# RS485_Demo_Bord_v1_0_-.net
KiCad netlist of a schematic drawn in Altium Designer
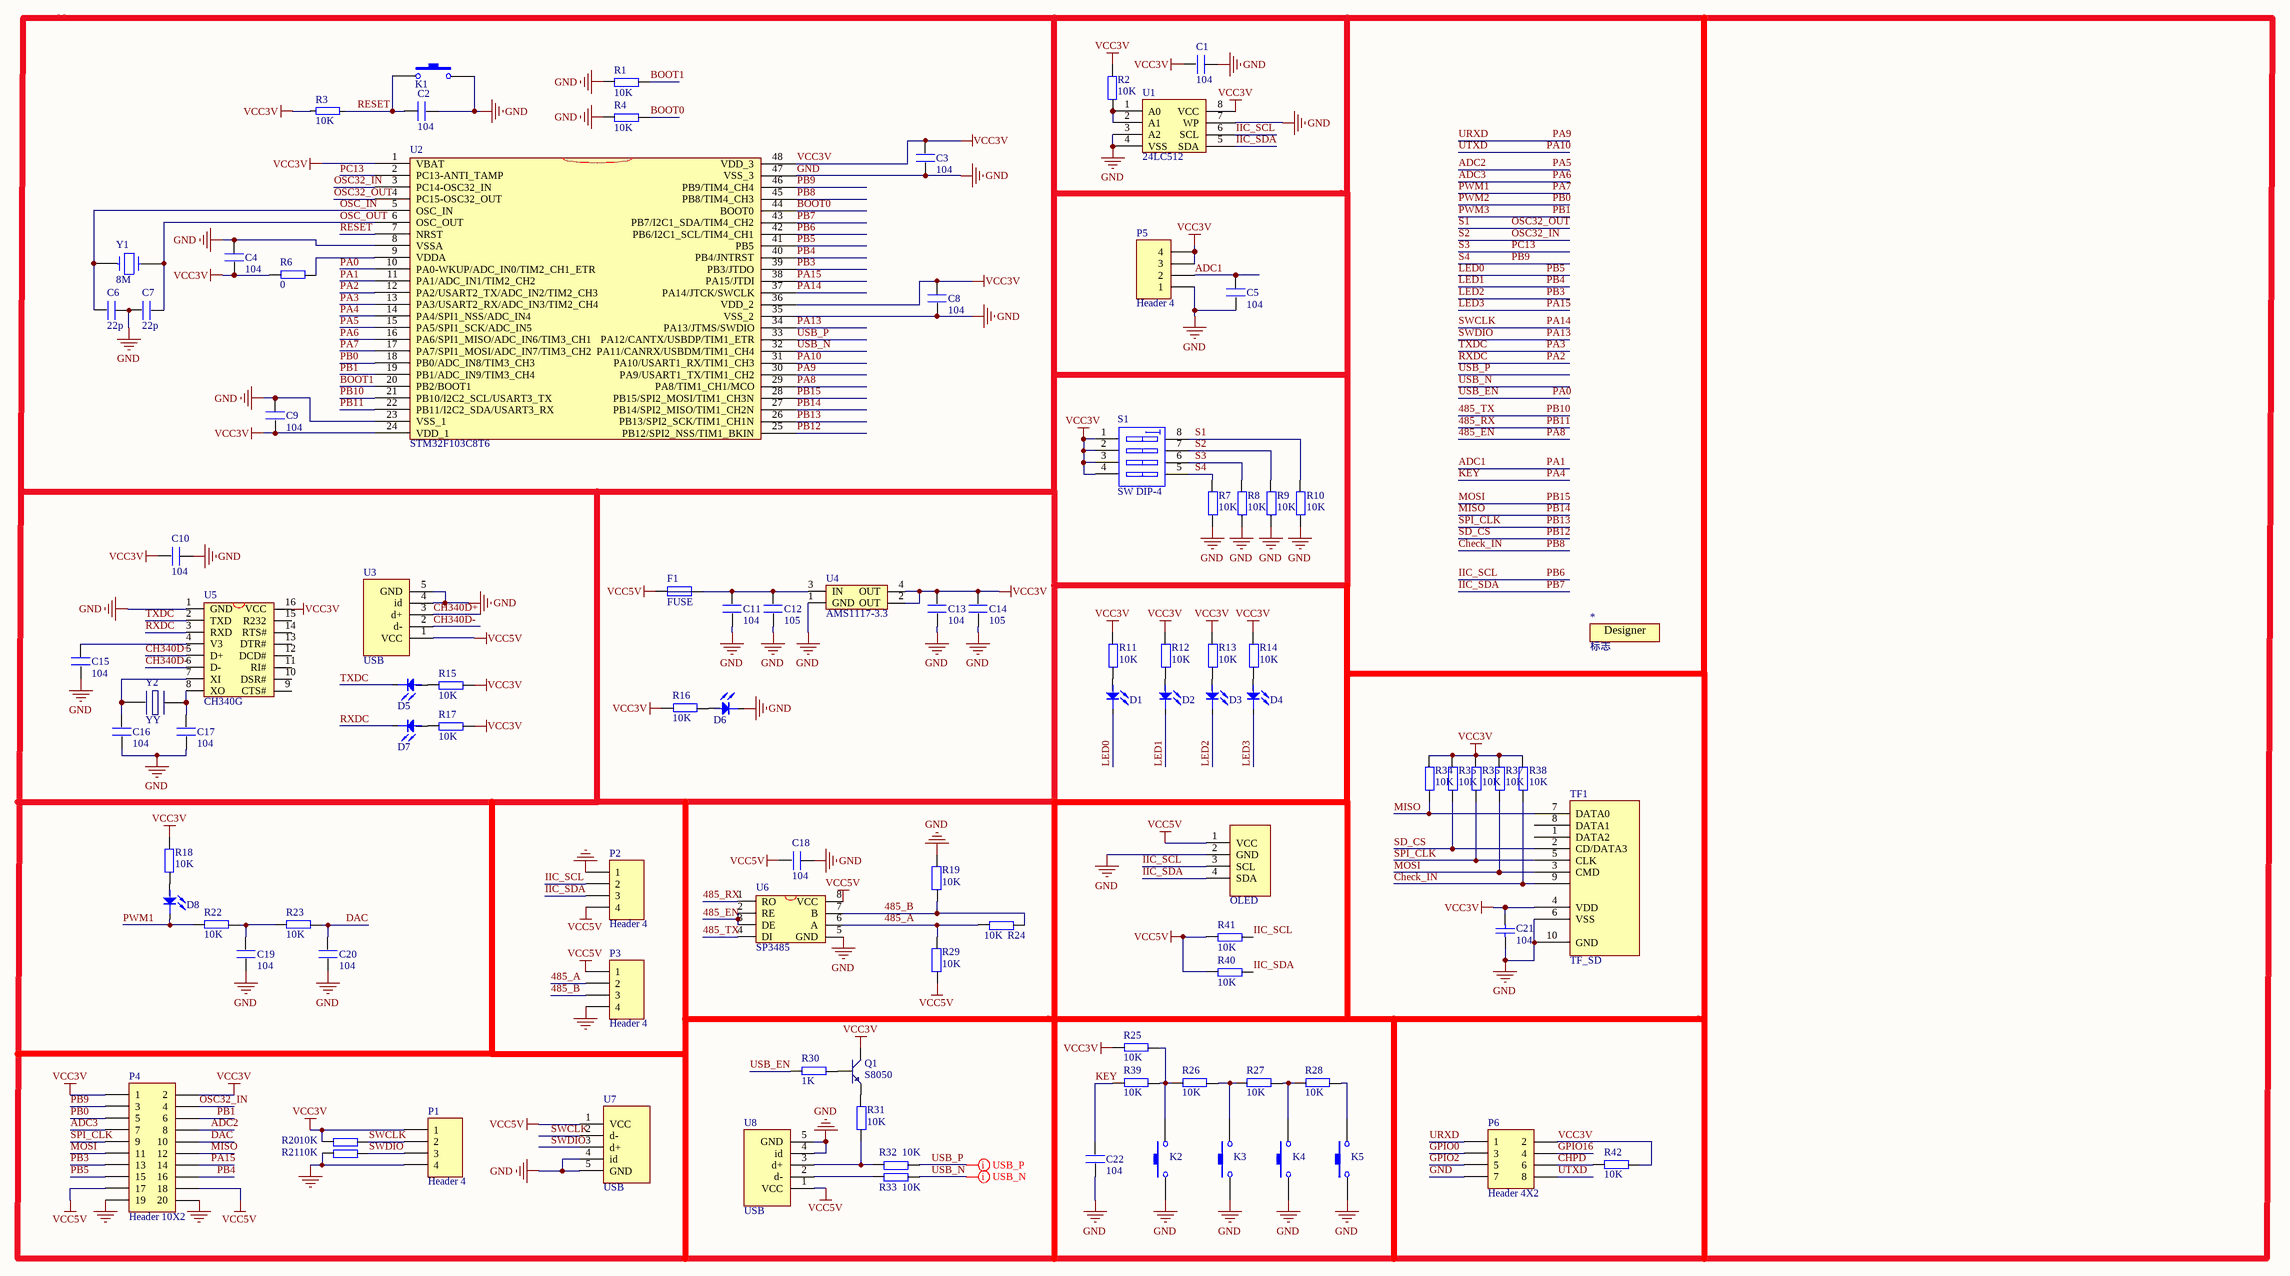
[diagram p0: RS485_Demo_Bord_v1.0 - 副本.SchDoc]

(export (version "E")
  (design (tool "Eeschema 10.0.6"))
  (components
    (comp (ref "*") (value "标志") (footprint "Designer - 1") (libsource (lib "Mylib") (part "标志")))
    (comp (ref "C1") (value "104") (footprint "C_0805") (libsource (lib "Mylib") (part "C")))
    (comp (ref "C2") (value "104") (footprint "C_0805") (libsource (lib "Mylib") (part "C")))
    (comp (ref "C3") (value "104") (footprint "C_0805") (libsource (lib "Mylib") (part "C")))
    (comp (ref "C4") (value "104") (footprint "C_0805") (libsource (lib "Mylib") (part "C")))
    (comp (ref "C5") (value "104") (footprint "C_0805") (libsource (lib "Mylib") (part "C")))
    (comp (ref "C6") (value "22p") (footprint "C_0805") (libsource (lib "Mylib") (part "C")))
    (comp (ref "C7") (value "22p") (footprint "C_0805") (libsource (lib "Mylib") (part "C")))
    (comp (ref "C8") (value "104") (footprint "C_0805") (libsource (lib "Mylib") (part "C")))
    (comp (ref "C9") (value "104") (footprint "C_0805") (libsource (lib "Mylib") (part "C")))
    (comp (ref "C10") (value "104") (footprint "C_0805") (libsource (lib "Mylib") (part "C")))
    (comp (ref "C11") (value "104") (footprint "C_0805") (libsource (lib "Mylib") (part "C")))
    (comp (ref "C12") (value "105") (footprint "C_0805") (libsource (lib "Mylib") (part "C")))
    (comp (ref "C13") (value "104") (footprint "C_0805") (libsource (lib "Mylib") (part "C")))
    (comp (ref "C14") (value "105") (footprint "C_0805") (libsource (lib "Mylib") (part "C")))
    (comp (ref "C15") (value "104") (footprint "C_0805") (libsource (lib "Mylib") (part "C")))
    (comp (ref "C16") (value "104") (footprint "C_0805") (libsource (lib "Mylib") (part "C")))
    (comp (ref "C17") (value "104") (footprint "C_0805") (libsource (lib "Mylib") (part "C")))
    (comp (ref "C18") (value "104") (footprint "C_0805") (libsource (lib "Mylib") (part "C")))
    (comp (ref "C19") (value "104") (footprint "C_0805") (libsource (lib "Mylib") (part "C")))
    (comp (ref "C20") (value "104") (footprint "C_0805") (libsource (lib "Mylib") (part "C")))
    (comp (ref "C21")
      (value "104")
      (footprint "0805C")
      (description "Capacitor")
      (fields (field (name "PUBLISHER") "Altium Limited"))
      (libsource (lib "STM32F407VET6mini最小系统-原理图库") (part "Cap"))
    )
    (comp (ref "C22") (value "104") (footprint "C_0805") (libsource (lib "Mylib") (part "C")))
    (comp (ref "D1") (value "LED") (footprint "0805-LED-RED") (libsource (lib "MY SCH LIB") (part "LED")))
    (comp (ref "D2") (value "LED") (footprint "0805-LED-RED") (libsource (lib "MY SCH LIB") (part "LED")))
    (comp (ref "D3") (value "LED") (footprint "0805-LED-RED") (libsource (lib "MY SCH LIB") (part "LED")))
    (comp (ref "D4") (value "LED") (footprint "0805-LED-RED") (libsource (lib "MY SCH LIB") (part "LED")))
    (comp (ref "D5") (value "LED") (footprint "0805-LED-RED") (libsource (lib "MY SCH LIB") (part "LED")))
    (comp (ref "D6") (value "LED") (footprint "0805-LED-RED") (libsource (lib "MY SCH LIB") (part "LED")))
    (comp (ref "D7") (value "LED") (footprint "0805-LED-RED") (libsource (lib "MY SCH LIB") (part "LED")))
    (comp (ref "D8") (value "LED") (footprint "0805-LED-RED") (libsource (lib "MY SCH LIB") (part "LED")))
    (comp (ref "F1") (value "FUSE") (footprint "0805") (libsource (lib "Mylib") (part "FUSE")))
    (comp (ref "K1") (value "KEY") (footprint "KEY_6") (libsource (lib "MY SCH LIB") (part "KEY")))
    (comp (ref "K2") (value "KEY") (footprint "KEY_6") (libsource (lib "MY SCH LIB") (part "KEY")))
    (comp (ref "K3") (value "KEY") (footprint "KEY_6") (libsource (lib "MY SCH LIB") (part "KEY")))
    (comp (ref "K4") (value "KEY") (footprint "KEY_6") (libsource (lib "MY SCH LIB") (part "KEY")))
    (comp (ref "K5") (value "KEY") (footprint "KEY_6") (libsource (lib "MY SCH LIB") (part "KEY")))
    (comp (ref "OLED")
      (value "OLED")
      (footprint "OLED__IIC_1")
      (libsource (lib "MY SCH LIB") (part "OLED_IIC_1"))
    )
    (comp (ref "P1")
      (value "Header 4")
      (footprint "XH_4_V")
      (description "Header, 4-Pin")
      (fields (field (name "PUBLISHER") "Altium Limited"))
      (libsource (lib "接口插座") (part "Header 4"))
    )
    (comp (ref "P2")
      (value "Header 4")
      (footprint "XH_4_V")
      (description "Header, 4-Pin")
      (fields (field (name "PUBLISHER") "Altium Limited"))
      (libsource (lib "接口插座") (part "Header 4"))
    )
    (comp (ref "P3")
      (value "Header 4")
      (footprint "XH_4_V")
      (description "Header, 4-Pin")
      (fields (field (name "PUBLISHER") "Altium Limited"))
      (libsource (lib "接口插座") (part "Header 4"))
    )
    (comp (ref "P4")
      (value "Header 10X2")
      (footprint "JTAG_20 - E")
      (description "Header, 10-Pin, Dual row")
      (fields (field (name "PUBLISHER") "Altium Limited"))
      (libsource (lib "接口插座") (part "Header 10X2"))
    )
    (comp (ref "P5")
      (value "Header 4")
      (footprint "XH_4_V")
      (description "Header, 4-Pin")
      (fields (field (name "PUBLISHER") "Altium Limited"))
      (libsource (lib "") (part "Header 4_1"))
    )
    (comp (ref "P6")
      (value "Header 4X2")
      (footprint "HDR2X4")
      (description "Header, 4-Pin, Dual row")
      (fields (field (name "PUBLISHER") "Altium Limited"))
      (libsource (lib "接口插座") (part "Header 4X2"))
    )
    (comp (ref "Q1") (value "S8050") (footprint "SOT23-3") (libsource (lib "Mylib") (part "NPN")))
    (comp (ref "R1") (value "10K") (footprint "0805") (libsource (lib "Mylib") (part "R")))
    (comp (ref "R2") (value "10K") (footprint "0805") (libsource (lib "Mylib") (part "R")))
    (comp (ref "R3") (value "10K") (footprint "0805") (libsource (lib "电阻") (part "RES")))
    (comp (ref "R4") (value "10K") (footprint "0805") (libsource (lib "Mylib") (part "R")))
    (comp (ref "R6") (value "0") (footprint "0805") (libsource (lib "Mylib") (part "R")))
    (comp (ref "R7") (value "10K") (footprint "0805") (libsource (lib "Mylib") (part "R")))
    (comp (ref "R8") (value "10K") (footprint "0805") (libsource (lib "Mylib") (part "R")))
    (comp (ref "R9") (value "10K") (footprint "0805") (libsource (lib "Mylib") (part "R")))
    (comp (ref "R10") (value "10K") (footprint "0805") (libsource (lib "Mylib") (part "R")))
    (comp (ref "R11") (value "10K") (footprint "0805") (libsource (lib "Mylib") (part "R")))
    (comp (ref "R12") (value "10K") (footprint "0805") (libsource (lib "Mylib") (part "R")))
    (comp (ref "R13") (value "10K") (footprint "0805") (libsource (lib "Mylib") (part "R")))
    (comp (ref "R14") (value "10K") (footprint "0805") (libsource (lib "Mylib") (part "R")))
    (comp (ref "R15") (value "10K") (footprint "0805") (libsource (lib "Mylib") (part "R")))
    (comp (ref "R16") (value "10K") (footprint "0805") (libsource (lib "Mylib") (part "R")))
    (comp (ref "R17") (value "10K") (footprint "0805") (libsource (lib "Mylib") (part "R")))
    (comp (ref "R18") (value "10K") (footprint "0805") (libsource (lib "Mylib") (part "R")))
    (comp (ref "R19") (value "10K") (footprint "0805") (libsource (lib "Mylib") (part "R")))
    (comp (ref "R20") (value "10K") (footprint "0805") (libsource (lib "Mylib") (part "R")))
    (comp (ref "R21") (value "10K") (footprint "0805") (libsource (lib "Mylib") (part "R")))
    (comp (ref "R22") (value "10K") (footprint "0805") (libsource (lib "Mylib") (part "R")))
    (comp (ref "R23") (value "10K") (footprint "0805") (libsource (lib "Mylib") (part "R")))
    (comp (ref "R24") (value "10K") (footprint "0805") (libsource (lib "Mylib") (part "R")))
    (comp (ref "R25") (value "10K") (footprint "0805") (libsource (lib "Mylib") (part "R")))
    (comp (ref "R26") (value "10K") (footprint "0805") (libsource (lib "Mylib") (part "R")))
    (comp (ref "R27") (value "10K") (footprint "0805") (libsource (lib "Mylib") (part "R")))
    (comp (ref "R28") (value "10K") (footprint "0805") (libsource (lib "Mylib") (part "R")))
    (comp (ref "R29") (value "10K") (footprint "0805") (libsource (lib "Mylib") (part "R")))
    (comp (ref "R30") (value "1K") (footprint "0805") (libsource (lib "Mylib") (part "R")))
    (comp (ref "R31") (value "10K") (footprint "0805") (libsource (lib "Mylib") (part "R")))
    (comp (ref "R32") (value "10K") (footprint "0805") (libsource (lib "Mylib") (part "R")))
    (comp (ref "R33") (value "10K") (footprint "0805") (libsource (lib "Mylib") (part "R")))
    (comp (ref "R34") (value "10K") (footprint "0805") (libsource (lib "Mylib") (part "R")))
    (comp (ref "R35") (value "10K") (footprint "0805") (libsource (lib "Mylib") (part "R")))
    (comp (ref "R36") (value "10K") (footprint "0805") (libsource (lib "Mylib") (part "R")))
    (comp (ref "R37") (value "10K") (footprint "0805") (libsource (lib "Mylib") (part "R")))
    (comp (ref "R38") (value "10K") (footprint "0805") (libsource (lib "Mylib") (part "R")))
    (comp (ref "R39") (value "10K") (footprint "0805") (libsource (lib "Mylib") (part "R")))
    (comp (ref "R40") (value "10K") (footprint "0805") (libsource (lib "Mylib") (part "R")))
    (comp (ref "R41") (value "10K") (footprint "0805") (libsource (lib "Mylib") (part "R")))
    (comp (ref "R42") (value "10K") (footprint "0805") (libsource (lib "Mylib") (part "R")))
    (comp (ref "S1")
      (value "SW DIP-4")
      (footprint "SWITCH_DIP-4")
      (description "DIP Switch")
      (libsource (lib "MY SCH LIB") (part "SW DIP-4"))
    )
    (comp (ref "TF1") (value "TF_SD") (footprint "TF_SD") (libsource (lib "stm32f103vet6") (part "TF_SD")))
    (comp (ref "U1") (value "24LC512") (footprint "SO-8") (libsource (lib "Mylib") (part "24LC512")))
    (comp (ref "U2")
      (value "STM32F103C8T6")
      (footprint "LQFP-48_M")
      (libsource (lib "stm32") (part "STM32F103C6"))
    )
    (comp (ref "U3") (value "USB") (footprint "USB_MICRO_F") (libsource (lib "") (part "USB_1")))
    (comp (ref "U4")
      (value "AMS1117-3.3")
      (footprint "SOT223")
      (libsource (lib "MY SCH LIB") (part "AMS1117"))
    )
    (comp (ref "U5") (value "CH340G") (footprint "SO-16") (libsource (lib "Mylib") (part "CH340G")))
    (comp (ref "U6")
      (value "SP3485")
      (footprint "SOP-8")
      (libsource (lib "战舰STM32开发板底板封装库") (part "MAX3485"))
    )
    (comp (ref "U7") (value "USB") (footprint "USB_MICRO_F") (libsource (lib "MY SCH LIB") (part "USB")))
    (comp (ref "U8") (value "USB") (footprint "USB_MICRO_F") (libsource (lib "") (part "USB_1")))
    (comp (ref "Y1")
      (value "8M")
      (footprint "XTAL-3")
      (description "Crystal")
      (libsource (lib "MY SCH LIB") (part "CRYSTAL"))
    )
    (comp (ref "Y2") (value "YY") (footprint "XTAL-3") (libsource (lib "Mylib") (part "YY")))
  )
  (nets
    (net (code "1") (name "/485_A") (class "Default")
      (node (ref "P3") (pin "2") (pinfunction "2_2") (pintype "passive"))
      (node (ref "R24") (pin "1") (pintype "passive"))
      (node (ref "R29") (pin "1") (pintype "passive"))
      (node (ref "U6") (pin "6") (pinfunction "A_6") (pintype "passive"))
    )
    (net (code "2") (name "/485_B") (class "Default")
      (node (ref "P3") (pin "3") (pinfunction "3_3") (pintype "passive"))
      (node (ref "R19") (pin "2") (pintype "passive"))
      (node (ref "R24") (pin "2") (pintype "passive"))
      (node (ref "U6") (pin "7") (pinfunction "B_7") (pintype "passive"))
    )
    (net (code "3") (name "/485_EN") (class "Default")
      (node (ref "U2") (pin "29") (pinfunction "PA8/TIM1_CH1/MCO_29") (pintype "passive"))
      (node (ref "U6") (pin "2") (pinfunction "RE_2") (pintype "passive"))
      (node (ref "U6") (pin "3") (pinfunction "DE_3") (pintype "passive"))
    )
    (net (code "4") (name "/485_RX") (class "Default")
      (node (ref "U2") (pin "22") (pinfunction "PB11/I2C2_SDA/USART3_RX_22") (pintype "passive"))
      (node (ref "U6") (pin "1") (pinfunction "RO_1") (pintype "passive"))
    )
    (net (code "5") (name "/485_TX") (class "Default")
      (node (ref "U2") (pin "21") (pinfunction "PB10/I2C2_SCL/USART3_TX_21") (pintype "passive"))
      (node (ref "U6") (pin "4") (pinfunction "DI_4") (pintype "passive"))
    )
    (net (code "6") (name "/ADC1") (class "Default")
      (node (ref "C5") (pin "2") (pintype "passive"))
      (node (ref "P5") (pin "2") (pinfunction "2_2") (pintype "passive"))
      (node (ref "U2") (pin "11") (pinfunction "PA1/ADC_IN1/TIM2_CH2_11") (pintype "passive"))
    )
    (net (code "7") (name "/ADC2") (class "Default")
      (node (ref "P4") (pin "8") (pinfunction "8_8") (pintype "passive"))
      (node (ref "U2") (pin "15") (pinfunction "PA5/SPI1_SCK/ADC_IN5_15") (pintype "passive"))
    )
    (net (code "8") (name "/ADC3") (class "Default")
      (node (ref "P4") (pin "7") (pinfunction "7_7") (pintype "passive"))
      (node (ref "U2") (pin "16") (pinfunction "PA6/SPI1_MISO/ADC_IN6/TIM3_CH1_16") (pintype "passive"))
    )
    (net (code "9") (name "/BOOT0") (class "Default")
      (node (ref "R4") (pin "2") (pintype "passive"))
      (node (ref "U2") (pin "44") (pinfunction "BOOT0_44") (pintype "passive"))
    )
    (net (code "10") (name "/BOOT1") (class "Default")
      (node (ref "R1") (pin "2") (pintype "passive"))
      (node (ref "U2") (pin "20") (pinfunction "PB2/BOOT1_20") (pintype "passive"))
    )
    (net (code "11") (name "/CH340D+") (class "Default")
      (node (ref "U3") (pin "3") (pinfunction "d+_3") (pintype "passive"))
      (node (ref "U5") (pin "5") (pinfunction "D+_5") (pintype "passive"))
    )
    (net (code "12") (name "/CH340D-") (class "Default")
      (node (ref "U3") (pin "2") (pinfunction "d-_2") (pintype "passive"))
      (node (ref "U5") (pin "6") (pinfunction "D-_6") (pintype "passive"))
    )
    (net (code "13") (name "/CHPD") (class "Default")
      (node (ref "P6") (pin "6") (pinfunction "6_6") (pintype "passive"))
      (node (ref "R42") (pin "2") (pintype "passive"))
    )
    (net (code "14") (name "/Check_IN") (class "Default")
      (node (ref "R38") (pin "1") (pintype "passive"))
      (node (ref "TF1") (pin "9") (pinfunction "VSS_9") (pintype "passive"))
      (node (ref "U2") (pin "45") (pinfunction "PB8/TIM4_CH3_45") (pintype "passive"))
    )
    (net (code "15") (name "/DAC") (class "Default")
      (node (ref "C20") (pin "2") (pintype "passive"))
      (node (ref "P4") (pin "10") (pinfunction "10_10") (pintype "passive"))
      (node (ref "R23") (pin "1") (pintype "passive"))
    )
    (net (code "16") (name "/GPIO0") (class "Default")
      (node (ref "P6") (pin "3") (pinfunction "3_3") (pintype "passive"))
    )
    (net (code "17") (name "/GPIO2") (class "Default")
      (node (ref "P6") (pin "5") (pinfunction "5_5") (pintype "passive"))
    )
    (net (code "18") (name "/GPIO16") (class "Default")
      (node (ref "P6") (pin "4") (pinfunction "4_4") (pintype "passive"))
    )
    (net (code "19") (name "/IIC_SCL") (class "Default")
      (node (ref "OLED") (pin "3") (pinfunction "SCL_3") (pintype "passive"))
      (node (ref "P2") (pin "2") (pinfunction "2_2") (pintype "passive"))
      (node (ref "R41") (pin "2") (pintype "passive"))
      (node (ref "U1") (pin "6") (pinfunction "SCL_6") (pintype "passive"))
      (node (ref "U2") (pin "42") (pinfunction "PB6/I2C1_SCL/TIM4_CH1_42") (pintype "passive"))
    )
    (net (code "20") (name "/IIC_SDA") (class "Default")
      (node (ref "OLED") (pin "4") (pinfunction "SDA_4") (pintype "passive"))
      (node (ref "P2") (pin "3") (pinfunction "3_3") (pintype "passive"))
      (node (ref "R40") (pin "2") (pintype "passive"))
      (node (ref "U1") (pin "5") (pinfunction "SDA_5") (pintype "passive"))
      (node (ref "U2") (pin "43") (pinfunction "PB7/I2C1_SDA/TIM4_CH2_43") (pintype "passive"))
    )
    (net (code "21") (name "/KEY") (class "Default")
      (node (ref "C22") (pin "2") (pintype "passive"))
      (node (ref "R39") (pin "2") (pintype "passive"))
      (node (ref "U2") (pin "14") (pinfunction "PA4/SPI1_NSS/ADC_IN4_14") (pintype "passive"))
    )
    (net (code "22") (name "/LED0") (class "Default")
      (node (ref "D1") (pin "K") (pintype "passive"))
      (node (ref "P4") (pin "15") (pinfunction "15_15") (pintype "passive"))
      (node (ref "U2") (pin "41") (pinfunction "PB5_41") (pintype "passive"))
    )
    (net (code "23") (name "/LED1") (class "Default")
      (node (ref "D2") (pin "K") (pintype "passive"))
      (node (ref "P4") (pin "16") (pinfunction "16_16") (pintype "passive"))
      (node (ref "U2") (pin "40") (pinfunction "PB4/JNTRST_40") (pintype "passive"))
    )
    (net (code "24") (name "/LED2") (class "Default")
      (node (ref "D3") (pin "K") (pintype "passive"))
      (node (ref "P4") (pin "13") (pinfunction "13_13") (pintype "passive"))
      (node (ref "U2") (pin "39") (pinfunction "PB3/JTDO_39") (pintype "passive"))
    )
    (net (code "25") (name "/LED3") (class "Default")
      (node (ref "D4") (pin "K") (pintype "passive"))
      (node (ref "P4") (pin "14") (pinfunction "14_14") (pintype "passive"))
      (node (ref "U2") (pin "38") (pinfunction "PA15/JTDI_38") (pintype "passive"))
    )
    (net (code "26") (name "/MISO") (class "Default")
      (node (ref "P4") (pin "12") (pinfunction "12_12") (pintype "passive"))
      (node (ref "R34") (pin "1") (pintype "passive"))
      (node (ref "TF1") (pin "7") (pinfunction "DATA0_7") (pintype "passive"))
      (node (ref "U2") (pin "27") (pinfunction "PB14/SPI2_MISO/TIM1_CH2N_27") (pintype "passive"))
    )
    (net (code "27") (name "/MOSI") (class "Default")
      (node (ref "P4") (pin "11") (pinfunction "11_11") (pintype "passive"))
      (node (ref "R37") (pin "1") (pintype "passive"))
      (node (ref "TF1") (pin "3") (pinfunction "CMD_3") (pintype "passive"))
      (node (ref "U2") (pin "28") (pinfunction "PB15/SPI2_MOSI/TIM1_CH3N_28") (pintype "passive"))
    )
    (net (code "28") (name "/OSC32_IN") (class "Default")
      (node (ref "P4") (pin "4") (pinfunction "4_4") (pintype "passive"))
      (node (ref "R9") (pin "2") (pintype "passive"))
      (node (ref "S1") (pin "7") (pinfunction "B2_7") (pintype "passive"))
      (node (ref "U2") (pin "3") (pinfunction "PC14-OSC32_IN_3") (pintype "passive"))
    )
    (net (code "29") (name "/OSC32_OUT") (class "Default")
      (node (ref "R10") (pin "2") (pintype "passive"))
      (node (ref "S1") (pin "8") (pinfunction "B1_8") (pintype "passive"))
      (node (ref "U2") (pin "4") (pinfunction "PC15-OSC32_OUT_4") (pintype "passive"))
    )
    (net (code "30") (name "/OSC_IN") (class "Default")
      (node (ref "C6") (pin "2") (pintype "passive"))
      (node (ref "U2") (pin "5") (pinfunction "OSC_IN_5") (pintype "passive"))
      (node (ref "Y1") (pin "1") (pinfunction "1_1") (pintype "passive"))
    )
    (net (code "31") (name "/OSC_OUT") (class "Default")
      (node (ref "C7") (pin "1") (pintype "passive"))
      (node (ref "U2") (pin "6") (pinfunction "OSC_OUT_6") (pintype "passive"))
      (node (ref "Y1") (pin "2") (pinfunction "2_2") (pintype "passive"))
    )
    (net (code "32") (name "/PA0") (class "Default")
      (node (ref "R30") (pin "2") (pintype "passive"))
      (node (ref "U2") (pin "10") (pinfunction "PA0-WKUP/ADC_IN0/TIM2_CH1_ETR_10") (pintype "passive"))
    )
    (net (code "33") (name "/PA2") (class "Default")
      (node (ref "D7") (pin "K") (pintype "passive"))
      (node (ref "U2") (pin "12") (pinfunction "PA2/USART2_TX/ADC_IN2/TIM2_CH3_12") (pintype "passive"))
      (node (ref "U5") (pin "3") (pinfunction "RXD_3") (pintype "passive"))
    )
    (net (code "34") (name "/PA3") (class "Default")
      (node (ref "D5") (pin "K") (pintype "passive"))
      (node (ref "U2") (pin "13") (pinfunction "PA3/USART2_RX/ADC_IN3/TIM2_CH4_13") (pintype "passive"))
      (node (ref "U5") (pin "2") (pinfunction "TXD_2") (pintype "passive"))
    )
    (net (code "35") (name "/PA7") (class "Default")
      (node (ref "D8") (pin "K") (pintype "passive"))
      (node (ref "R22") (pin "2") (pintype "passive"))
      (node (ref "U2") (pin "17") (pinfunction "PA7/SPI1_MOSI/ADC_IN7/TIM3_CH2_17") (pintype "passive"))
    )
    (net (code "36") (name "/PA9") (class "Default")
      (node (ref "P6") (pin "1") (pinfunction "1_1") (pintype "passive"))
      (node (ref "U2") (pin "30") (pinfunction "PA9/USART1_TX/TIM1_CH2_30") (pintype "passive"))
    )
    (net (code "37") (name "/PA10") (class "Default")
      (node (ref "P6") (pin "8") (pinfunction "8_8") (pintype "passive"))
      (node (ref "U2") (pin "31") (pinfunction "PA10/USART1_RX/TIM1_CH3_31") (pintype "passive"))
    )
    (net (code "38") (name "/PA13") (class "Default")
      (node (ref "P1") (pin "3") (pinfunction "3_3") (pintype "passive"))
      (node (ref "R21") (pin "2") (pintype "passive"))
      (node (ref "U2") (pin "34") (pinfunction "PA13/JTMS/SWDIO_34") (pintype "passive"))
      (node (ref "U7") (pin "3") (pinfunction "d+_3") (pintype "passive"))
    )
    (net (code "39") (name "/PA14") (class "Default")
      (node (ref "P1") (pin "2") (pinfunction "2_2") (pintype "passive"))
      (node (ref "R20") (pin "2") (pintype "passive"))
      (node (ref "U2") (pin "37") (pinfunction "PA14/JTCK/SWCLK_37") (pintype "passive"))
      (node (ref "U7") (pin "2") (pinfunction "d-_2") (pintype "passive"))
    )
    (net (code "40") (name "/PB0") (class "Default")
      (node (ref "P4") (pin "5") (pinfunction "5_5") (pintype "passive"))
      (node (ref "U2") (pin "18") (pinfunction "PB0/ADC_IN8/TIM3_CH3_18") (pintype "passive"))
    )
    (net (code "41") (name "/PB1") (class "Default")
      (node (ref "P4") (pin "6") (pinfunction "6_6") (pintype "passive"))
      (node (ref "U2") (pin "19") (pinfunction "PB1/ADC_IN9/TIM3_CH4_19") (pintype "passive"))
    )
    (net (code "42") (name "/PB9") (class "Default")
      (node (ref "P4") (pin "3") (pinfunction "3_3") (pintype "passive"))
      (node (ref "R7") (pin "2") (pintype "passive"))
      (node (ref "S1") (pin "5") (pinfunction "B4_5") (pintype "passive"))
      (node (ref "U2") (pin "46") (pinfunction "PB9/TIM4_CH4_46") (pintype "passive"))
    )
    (net (code "43") (name "/PB12") (class "Default")
      (node (ref "R35") (pin "1") (pintype "passive"))
      (node (ref "TF1") (pin "2") (pinfunction "CD/DATA3_2") (pintype "passive"))
      (node (ref "U2") (pin "25") (pinfunction "PB12/SPI2_NSS/TIM1_BKIN_25") (pintype "passive"))
    )
    (net (code "44") (name "/PB13") (class "Default")
      (node (ref "P4") (pin "9") (pinfunction "9_9") (pintype "passive"))
      (node (ref "R36") (pin "1") (pintype "passive"))
      (node (ref "TF1") (pin "5") (pinfunction "CLK_5") (pintype "passive"))
      (node (ref "U2") (pin "26") (pinfunction "PB13/SPI2_SCK/TIM1_CH1N_26") (pintype "passive"))
    )
    (net (code "45") (name "/PC13") (class "Default")
      (node (ref "R8") (pin "2") (pintype "passive"))
      (node (ref "S1") (pin "6") (pinfunction "B3_6") (pintype "passive"))
      (node (ref "U2") (pin "2") (pinfunction "PC13-ANTI_TAMP_2") (pintype "passive"))
    )
    (net (code "46") (name "/RESET") (class "Default")
      (node (ref "C2") (pin "1") (pintype "passive"))
      (node (ref "K1") (pin "1") (pinfunction "1_1") (pintype "passive"))
      (node (ref "R3") (pin "1") (pinfunction "1_1") (pintype "passive"))
      (node (ref "U2") (pin "7") (pinfunction "NRST_7") (pintype "passive"))
    )
    (net (code "47") (name "/USB_N") (class "Default")
      (node (ref "R33") (pin "2") (pintype "passive"))
      (node (ref "U2") (pin "32") (pinfunction "PA11/CANRX/USBDM/TIM1_CH4_32") (pintype "passive"))
    )
    (net (code "48") (name "/USB_P") (class "Default")
      (node (ref "R32") (pin "2") (pintype "passive"))
      (node (ref "U2") (pin "33") (pinfunction "PA12/CANTX/USBDP/TIM1_ETR_33") (pintype "passive"))
    )
    (net (code "49") (name "GND") (class "Default")
      (node (ref "C1") (pin "1") (pintype "passive"))
      (node (ref "C10") (pin "1") (pintype "passive"))
      (node (ref "C11") (pin "1") (pintype "passive"))
      (node (ref "C12") (pin "1") (pintype "passive"))
      (node (ref "C13") (pin "1") (pintype "passive"))
      (node (ref "C14") (pin "1") (pintype "passive"))
      (node (ref "C15") (pin "1") (pintype "passive"))
      (node (ref "C16") (pin "1") (pintype "passive"))
      (node (ref "C17") (pin "1") (pintype "passive"))
      (node (ref "C18") (pin "1") (pintype "passive"))
      (node (ref "C19") (pin "1") (pintype "passive"))
      (node (ref "C2") (pin "2") (pintype "passive"))
      (node (ref "C20") (pin "1") (pintype "passive"))
      (node (ref "C21") (pin "1") (pinfunction "1_1") (pintype "passive"))
      (node (ref "C22") (pin "1") (pintype "passive"))
      (node (ref "C3") (pin "1") (pintype "passive"))
      (node (ref "C4") (pin "2") (pintype "passive"))
      (node (ref "C5") (pin "1") (pintype "passive"))
      (node (ref "C6") (pin "1") (pintype "passive"))
      (node (ref "C7") (pin "2") (pintype "passive"))
      (node (ref "C8") (pin "1") (pintype "passive"))
      (node (ref "C9") (pin "2") (pintype "passive"))
      (node (ref "D6") (pin "K") (pintype "passive"))
      (node (ref "K1") (pin "2") (pinfunction "2_2") (pintype "passive"))
      (node (ref "K2") (pin "1") (pinfunction "1_1") (pintype "passive"))
      (node (ref "K3") (pin "1") (pinfunction "1_1") (pintype "passive"))
      (node (ref "K4") (pin "1") (pinfunction "1_1") (pintype "passive"))
      (node (ref "K5") (pin "1") (pinfunction "1_1") (pintype "passive"))
      (node (ref "OLED") (pin "2") (pinfunction "GND_2") (pintype "passive"))
      (node (ref "P1") (pin "4") (pinfunction "4_4") (pintype "passive"))
      (node (ref "P2") (pin "1") (pinfunction "1_1") (pintype "passive"))
      (node (ref "P3") (pin "4") (pinfunction "4_4") (pintype "passive"))
      (node (ref "P4") (pin "19") (pinfunction "19_19") (pintype "passive"))
      (node (ref "P4") (pin "20") (pinfunction "20_20") (pintype "passive"))
      (node (ref "P5") (pin "1") (pinfunction "1_1") (pintype "passive"))
      (node (ref "P6") (pin "7") (pinfunction "7_7") (pintype "passive"))
      (node (ref "R1") (pin "1") (pintype "passive"))
      (node (ref "R10") (pin "1") (pintype "passive"))
      (node (ref "R19") (pin "1") (pintype "passive"))
      (node (ref "R21") (pin "1") (pintype "passive"))
      (node (ref "R4") (pin "1") (pintype "passive"))
      (node (ref "R7") (pin "1") (pintype "passive"))
      (node (ref "R8") (pin "1") (pintype "passive"))
      (node (ref "R9") (pin "1") (pintype "passive"))
      (node (ref "TF1") (pin "10") (pinfunction "GND_10") (pintype "passive"))
      (node (ref "TF1") (pin "6") (pinfunction "VSS_6") (pintype "passive"))
      (node (ref "U1") (pin "3") (pinfunction "A2_3") (pintype "passive"))
      (node (ref "U1") (pin "4") (pinfunction "VSS_4") (pintype "passive"))
      (node (ref "U1") (pin "7") (pinfunction "WP_7") (pintype "passive"))
      (node (ref "U2") (pin "23") (pinfunction "VSS_1_23") (pintype "passive"))
      (node (ref "U2") (pin "35") (pinfunction "VSS_2_35") (pintype "passive"))
      (node (ref "U2") (pin "47") (pinfunction "VSS_3_47") (pintype "passive"))
      (node (ref "U2") (pin "8") (pinfunction "VSSA_8") (pintype "passive"))
      (node (ref "U3") (pin "4") (pinfunction "id_4") (pintype "passive"))
      (node (ref "U3") (pin "5") (pinfunction "GND_5") (pintype "passive"))
      (node (ref "U4") (pin "1") (pinfunction "GND_1") (pintype "passive"))
      (node (ref "U5") (pin "1") (pinfunction "GND_1") (pintype "passive"))
      (node (ref "U6") (pin "5") (pinfunction "GND_5") (pintype "passive"))
      (node (ref "U7") (pin "4") (pinfunction "id_4") (pintype "passive"))
      (node (ref "U7") (pin "5") (pinfunction "GND_5") (pintype "passive"))
      (node (ref "U8") (pin "4") (pinfunction "id_4") (pintype "passive"))
      (node (ref "U8") (pin "5") (pinfunction "GND_5") (pintype "passive"))
    )
    (net (code "50") (name "Net-(C19-Pad2)") (class "Default")
      (node (ref "C19") (pin "2") (pintype "passive"))
      (node (ref "R22") (pin "1") (pintype "passive"))
      (node (ref "R23") (pin "2") (pintype "passive"))
    )
    (net (code "51") (name "Net-(D1-PadA)") (class "Default")
      (node (ref "D1") (pin "A") (pintype "passive"))
      (node (ref "R11") (pin "1") (pintype "passive"))
    )
    (net (code "52") (name "Net-(D2-PadA)") (class "Default")
      (node (ref "D2") (pin "A") (pintype "passive"))
      (node (ref "R12") (pin "1") (pintype "passive"))
    )
    (net (code "53") (name "Net-(D3-PadA)") (class "Default")
      (node (ref "D3") (pin "A") (pintype "passive"))
      (node (ref "R13") (pin "1") (pintype "passive"))
    )
    (net (code "54") (name "Net-(D4-PadA)") (class "Default")
      (node (ref "D4") (pin "A") (pintype "passive"))
      (node (ref "R14") (pin "1") (pintype "passive"))
    )
    (net (code "55") (name "Net-(D5-PadA)") (class "Default")
      (node (ref "D5") (pin "A") (pintype "passive"))
      (node (ref "R15") (pin "1") (pintype "passive"))
    )
    (net (code "56") (name "Net-(D6-PadA)") (class "Default")
      (node (ref "D6") (pin "A") (pintype "passive"))
      (node (ref "R16") (pin "1") (pintype "passive"))
    )
    (net (code "57") (name "Net-(D7-PadA)") (class "Default")
      (node (ref "D7") (pin "A") (pintype "passive"))
      (node (ref "R17") (pin "1") (pintype "passive"))
    )
    (net (code "58") (name "Net-(D8-PadA)") (class "Default")
      (node (ref "D8") (pin "A") (pintype "passive"))
      (node (ref "R18") (pin "2") (pintype "passive"))
    )
    (net (code "59") (name "Net-(K2-Pad2)") (class "Default")
      (node (ref "K2") (pin "2") (pinfunction "2_2") (pintype "passive"))
      (node (ref "R25") (pin "1") (pintype "passive"))
      (node (ref "R26") (pin "2") (pintype "passive"))
      (node (ref "R39") (pin "1") (pintype "passive"))
    )
    (net (code "60") (name "Net-(K3-Pad2)") (class "Default")
      (node (ref "K3") (pin "2") (pinfunction "2_2") (pintype "passive"))
      (node (ref "R26") (pin "1") (pintype "passive"))
      (node (ref "R27") (pin "2") (pintype "passive"))
    )
    (net (code "61") (name "Net-(K4-Pad2)") (class "Default")
      (node (ref "K4") (pin "2") (pinfunction "2_2") (pintype "passive"))
      (node (ref "R27") (pin "1") (pintype "passive"))
      (node (ref "R28") (pin "2") (pintype "passive"))
    )
    (net (code "62") (name "Net-(K5-Pad2)") (class "Default")
      (node (ref "K5") (pin "2") (pinfunction "2_2") (pintype "passive"))
      (node (ref "R28") (pin "1") (pintype "passive"))
    )
    (net (code "63") (name "Net-(Q1-B)") (class "Default")
      (node (ref "Q1") (pin "1") (pinfunction "B_1") (pintype "passive"))
      (node (ref "R30") (pin "1") (pintype "passive"))
    )
    (net (code "64") (name "Net-(Q1-E)") (class "Default")
      (node (ref "Q1") (pin "3") (pinfunction "E_3") (pintype "passive"))
      (node (ref "R31") (pin "2") (pintype "passive"))
    )
    (net (code "65") (name "Net-(U1-A0)") (class "Default")
      (node (ref "R2") (pin "2") (pintype "passive"))
      (node (ref "U1") (pin "1") (pinfunction "A0_1") (pintype "passive"))
      (node (ref "U1") (pin "2") (pinfunction "A1_2") (pintype "passive"))
    )
    (net (code "66") (name "Net-(U2-VDDA)") (class "Default")
      (node (ref "R6") (pin "1") (pintype "passive"))
      (node (ref "U2") (pin "9") (pinfunction "VDDA_9") (pintype "passive"))
    )
    (net (code "67") (name "Net-(U4-IN)") (class "Default")
      (node (ref "C11") (pin "2") (pintype "passive"))
      (node (ref "C12") (pin "2") (pintype "passive"))
      (node (ref "F1") (pin "2") (pintype "passive"))
      (node (ref "U4") (pin "3") (pinfunction "IN_3") (pintype "passive"))
    )
    (net (code "68") (name "Net-(U5-V3)") (class "Default")
      (node (ref "C15") (pin "2") (pintype "passive"))
      (node (ref "U5") (pin "4") (pinfunction "V3_4") (pintype "passive"))
    )
    (net (code "69") (name "Net-(U5-XI)") (class "Default")
      (node (ref "C16") (pin "2") (pintype "passive"))
      (node (ref "U5") (pin "7") (pinfunction "XI_7") (pintype "passive"))
      (node (ref "Y2") (pin "2") (pintype "passive"))
    )
    (net (code "70") (name "Net-(U5-XO)") (class "Default")
      (node (ref "C17") (pin "2") (pintype "passive"))
      (node (ref "U5") (pin "8") (pinfunction "XO_8") (pintype "passive"))
      (node (ref "Y2") (pin "1") (pintype "passive"))
    )
    (net (code "71") (name "Net-(U8-d+)") (class "Default")
      (node (ref "R31") (pin "1") (pintype "passive"))
      (node (ref "R32") (pin "1") (pintype "passive"))
      (node (ref "U8") (pin "3") (pinfunction "d+_3") (pintype "passive"))
    )
    (net (code "72") (name "Net-(U8-d-)") (class "Default")
      (node (ref "R33") (pin "1") (pintype "passive"))
      (node (ref "U8") (pin "2") (pinfunction "d-_2") (pintype "passive"))
    )
    (net (code "73") (name "VCC3V") (class "Default")
      (node (ref "C1") (pin "2") (pintype "passive"))
      (node (ref "C10") (pin "2") (pintype "passive"))
      (node (ref "C13") (pin "2") (pintype "passive"))
      (node (ref "C14") (pin "2") (pintype "passive"))
      (node (ref "C21") (pin "2") (pinfunction "2_2") (pintype "passive"))
      (node (ref "C3") (pin "2") (pintype "passive"))
      (node (ref "C4") (pin "1") (pintype "passive"))
      (node (ref "C8") (pin "2") (pintype "passive"))
      (node (ref "C9") (pin "1") (pintype "passive"))
      (node (ref "P1") (pin "1") (pinfunction "1_1") (pintype "passive"))
      (node (ref "P4") (pin "1") (pinfunction "1_1") (pintype "passive"))
      (node (ref "P4") (pin "2") (pinfunction "2_2") (pintype "passive"))
      (node (ref "P5") (pin "3") (pinfunction "3_3") (pintype "passive"))
      (node (ref "P5") (pin "4") (pinfunction "4_4") (pintype "passive"))
      (node (ref "P6") (pin "2") (pinfunction "2_2") (pintype "passive"))
      (node (ref "Q1") (pin "2") (pinfunction "C_2") (pintype "passive"))
      (node (ref "R11") (pin "2") (pintype "passive"))
      (node (ref "R12") (pin "2") (pintype "passive"))
      (node (ref "R13") (pin "2") (pintype "passive"))
      (node (ref "R14") (pin "2") (pintype "passive"))
      (node (ref "R15") (pin "2") (pintype "passive"))
      (node (ref "R16") (pin "2") (pintype "passive"))
      (node (ref "R17") (pin "2") (pintype "passive"))
      (node (ref "R18") (pin "1") (pintype "passive"))
      (node (ref "R2") (pin "1") (pintype "passive"))
      (node (ref "R20") (pin "1") (pintype "passive"))
      (node (ref "R25") (pin "2") (pintype "passive"))
      (node (ref "R3") (pin "2") (pinfunction "2_2") (pintype "passive"))
      (node (ref "R34") (pin "2") (pintype "passive"))
      (node (ref "R35") (pin "2") (pintype "passive"))
      (node (ref "R36") (pin "2") (pintype "passive"))
      (node (ref "R37") (pin "2") (pintype "passive"))
      (node (ref "R38") (pin "2") (pintype "passive"))
      (node (ref "R42") (pin "1") (pintype "passive"))
      (node (ref "R6") (pin "2") (pintype "passive"))
      (node (ref "S1") (pin "1") (pinfunction "A1_1") (pintype "passive"))
      (node (ref "S1") (pin "2") (pinfunction "A2_2") (pintype "passive"))
      (node (ref "S1") (pin "3") (pinfunction "A3_3") (pintype "passive"))
      (node (ref "S1") (pin "4") (pinfunction "A4_4") (pintype "passive"))
      (node (ref "TF1") (pin "4") (pinfunction "VDD_4") (pintype "passive"))
      (node (ref "U1") (pin "8") (pinfunction "VCC_8") (pintype "passive"))
      (node (ref "U2") (pin "1") (pinfunction "VBAT_1") (pintype "passive"))
      (node (ref "U2") (pin "24") (pinfunction "VDD_1_24") (pintype "passive"))
      (node (ref "U2") (pin "36") (pinfunction "VDD_2_36") (pintype "passive"))
      (node (ref "U2") (pin "48") (pinfunction "VDD_3_48") (pintype "passive"))
      (node (ref "U4") (pin "2") (pinfunction "OUT_2") (pintype "passive"))
      (node (ref "U4") (pin "4") (pinfunction "OUT_4") (pintype "passive"))
      (node (ref "U5") (pin "16") (pinfunction "VCC_16") (pintype "passive"))
    )
    (net (code "74") (name "VCC5V") (class "Default")
      (node (ref "C18") (pin "2") (pintype "passive"))
      (node (ref "F1") (pin "1") (pintype "passive"))
      (node (ref "OLED") (pin "1") (pinfunction "VCC_1") (pintype "passive"))
      (node (ref "P2") (pin "4") (pinfunction "4_4") (pintype "passive"))
      (node (ref "P3") (pin "1") (pinfunction "1_1") (pintype "passive"))
      (node (ref "P4") (pin "17") (pinfunction "17_17") (pintype "passive"))
      (node (ref "P4") (pin "18") (pinfunction "18_18") (pintype "passive"))
      (node (ref "R29") (pin "2") (pintype "passive"))
      (node (ref "R40") (pin "1") (pintype "passive"))
      (node (ref "R41") (pin "1") (pintype "passive"))
      (node (ref "U3") (pin "1") (pinfunction "VCC_1") (pintype "passive"))
      (node (ref "U6") (pin "8") (pinfunction "VCC_8") (pintype "passive"))
      (node (ref "U7") (pin "1") (pinfunction "VCC_1") (pintype "passive"))
      (node (ref "U8") (pin "1") (pinfunction "VCC_1") (pintype "passive"))
    )
    (net (code "75") (name "unconnected-(TF1-DATA1-Pad8)") (class "Default")
      (node (ref "TF1") (pin "8") (pinfunction "DATA1_8") (pintype "passive"))
    )
    (net (code "76") (name "unconnected-(TF1-DATA2-Pad1)") (class "Default")
      (node (ref "TF1") (pin "1") (pinfunction "DATA2_1") (pintype "passive"))
    )
    (net (code "77") (name "unconnected-(U5-CTS#-Pad9)") (class "Default")
      (node (ref "U5") (pin "9") (pinfunction "CTS#_9") (pintype "passive"))
    )
    (net (code "78") (name "unconnected-(U5-DCD#-Pad12)") (class "Default")
      (node (ref "U5") (pin "12") (pinfunction "DCD#_12") (pintype "passive"))
    )
    (net (code "79") (name "unconnected-(U5-DSR#-Pad10)") (class "Default")
      (node (ref "U5") (pin "10") (pinfunction "DSR#_10") (pintype "passive"))
    )
    (net (code "80") (name "unconnected-(U5-DTR#-Pad13)") (class "Default")
      (node (ref "U5") (pin "13") (pinfunction "DTR#_13") (pintype "passive"))
    )
    (net (code "81") (name "unconnected-(U5-R232-Pad15)") (class "Default")
      (node (ref "U5") (pin "15") (pinfunction "R232_15") (pintype "passive"))
    )
    (net (code "82") (name "unconnected-(U5-RI#-Pad11)") (class "Default")
      (node (ref "U5") (pin "11") (pinfunction "RI#_11") (pintype "passive"))
    )
    (net (code "83") (name "unconnected-(U5-RTS#-Pad14)") (class "Default")
      (node (ref "U5") (pin "14") (pinfunction "RTS#_14") (pintype "passive"))
    )
  )
)
